# Strain_To_Digital.net
KiCad netlist of a schematic drawn in Altium Designer
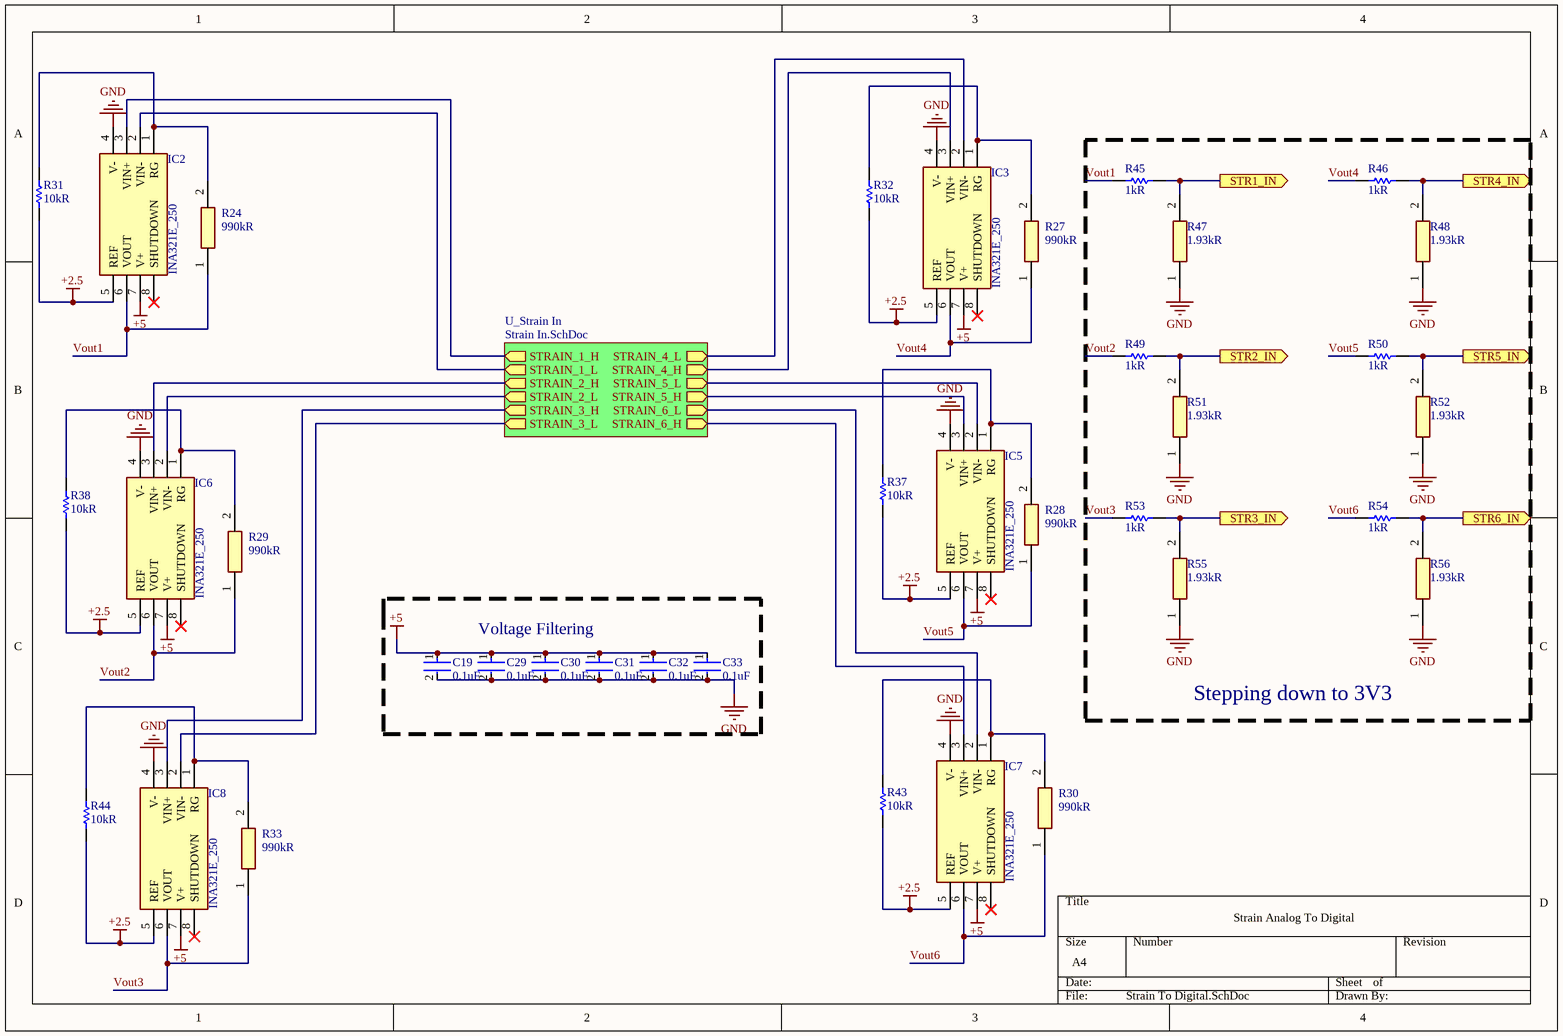
[diagram p0: Strain To Digital.SchDoc]

(export (version "E")
  (design (tool "Eeschema 10.0.6"))
  (components
    (comp (ref "C19")
      (value "0.1uF")
      (footprint "FP-CC0402-MFG")
      (description "CAP CER 0.1UF 16V X7R 0402")
      (fields (field (name "MANUFACTURER") "YAGEO") (field (name "TOLERANCE") "0.1"))
      (libsource (lib "Altium Content Vault") (part "11868f565c42a9108669ba33697ecf6"))
    )
    (comp (ref "C29")
      (value "0.1uF")
      (footprint "FP-CC0402-MFG")
      (description "CAP CER 0.1UF 16V X7R 0402")
      (fields (field (name "MANUFACTURER") "YAGEO") (field (name "TOLERANCE") "0.1"))
      (libsource (lib "Altium Content Vault") (part "11868f565c42a9108669ba33697ecf6"))
    )
    (comp (ref "C30")
      (value "0.1uF")
      (footprint "FP-CC0402-MFG")
      (description "CAP CER 0.1UF 16V X7R 0402")
      (fields (field (name "MANUFACTURER") "YAGEO") (field (name "TOLERANCE") "0.1"))
      (libsource (lib "Altium Content Vault") (part "11868f565c42a9108669ba33697ecf6"))
    )
    (comp (ref "C31")
      (value "0.1uF")
      (footprint "FP-CC0402-MFG")
      (description "CAP CER 0.1UF 16V X7R 0402")
      (fields (field (name "MANUFACTURER") "YAGEO") (field (name "TOLERANCE") "0.1"))
      (libsource (lib "Altium Content Vault") (part "11868f565c42a9108669ba33697ecf6"))
    )
    (comp (ref "C32")
      (value "0.1uF")
      (footprint "FP-CC0402-MFG")
      (description "CAP CER 0.1UF 16V X7R 0402")
      (fields (field (name "MANUFACTURER") "YAGEO") (field (name "TOLERANCE") "0.1"))
      (libsource (lib "Altium Content Vault") (part "11868f565c42a9108669ba33697ecf6"))
    )
    (comp (ref "C33")
      (value "0.1uF")
      (footprint "FP-CC0402-MFG")
      (description "CAP CER 0.1UF 16V X7R 0402")
      (fields (field (name "MANUFACTURER") "YAGEO") (field (name "TOLERANCE") "0.1"))
      (libsource (lib "Altium Content Vault") (part "11868f565c42a9108669ba33697ecf6"))
    )
    (comp (ref "IC2")
      (value "INA321E_250")
      (footprint "SamacSys:SOP65P490X110-8N")
      (description "Integrated Circuit")
      (fields (field (name "MANUFACTURER_PART_NUMBER") "INA321E/250"))
      (libsource (lib "*") (part "INA321E_250"))
    )
    (comp (ref "IC3")
      (value "INA321E_250")
      (footprint "SamacSys:SOP65P490X110-8N")
      (description "Integrated Circuit")
      (fields (field (name "MANUFACTURER_PART_NUMBER") "INA321E/250"))
      (libsource (lib "*") (part "INA321E_250"))
    )
    (comp (ref "IC5")
      (value "INA321E_250")
      (footprint "SamacSys:SOP65P490X110-8N")
      (description "Integrated Circuit")
      (fields (field (name "MANUFACTURER_PART_NUMBER") "INA321E/250"))
      (libsource (lib "*") (part "INA321E_250"))
    )
    (comp (ref "IC6")
      (value "INA321E_250")
      (footprint "SamacSys:SOP65P490X110-8N")
      (description "Integrated Circuit")
      (fields (field (name "MANUFACTURER_PART_NUMBER") "INA321E/250"))
      (libsource (lib "*") (part "INA321E_250"))
    )
    (comp (ref "IC7")
      (value "INA321E_250")
      (footprint "SamacSys:SOP65P490X110-8N")
      (description "Integrated Circuit")
      (fields (field (name "MANUFACTURER_PART_NUMBER") "INA321E/250"))
      (libsource (lib "*") (part "INA321E_250"))
    )
    (comp (ref "IC8")
      (value "INA321E_250")
      (footprint "SamacSys:SOP65P490X110-8N")
      (description "Integrated Circuit")
      (fields (field (name "MANUFACTURER_PART_NUMBER") "INA321E/250"))
      (libsource (lib "*") (part "INA321E_250"))
    )
    (comp (ref "R24")
      (value "990kR")
      (footprint "SamacSys:RESC3216X84N")
      (description "Resistor")
      (fields (field (name "MANUFACTURER_PART_NUMBER") "PTN1206E9903BST1"))
      (libsource (lib "*") (part "PTN1206E9903BST1"))
    )
    (comp (ref "R27")
      (value "990kR")
      (footprint "SamacSys:RESC3216X84N")
      (description "Resistor")
      (fields (field (name "MANUFACTURER_PART_NUMBER") "PTN1206E9903BST1"))
      (libsource (lib "*") (part "PTN1206E9903BST1"))
    )
    (comp (ref "R28")
      (value "990kR")
      (footprint "SamacSys:RESC3216X84N")
      (description "Resistor")
      (fields (field (name "MANUFACTURER_PART_NUMBER") "PTN1206E9903BST1"))
      (libsource (lib "*") (part "PTN1206E9903BST1"))
    )
    (comp (ref "R29")
      (value "990kR")
      (footprint "SamacSys:RESC3216X84N")
      (description "Resistor")
      (fields (field (name "MANUFACTURER_PART_NUMBER") "PTN1206E9903BST1"))
      (libsource (lib "*") (part "PTN1206E9903BST1"))
    )
    (comp (ref "R30")
      (value "990kR")
      (footprint "SamacSys:RESC3216X84N")
      (description "Resistor")
      (fields (field (name "MANUFACTURER_PART_NUMBER") "PTN1206E9903BST1"))
      (libsource (lib "*") (part "PTN1206E9903BST1"))
    )
    (comp (ref "R31")
      (value "10kR")
      (footprint "RESC1608X55X30ML20T20")
      (fields (field (name "PART NUMBER") "ERA-3AEB103V") (field (name "MANUFACTURER") "Panasonic"))
      (libsource (lib "Altium Content Vault") (part "RES"))
    )
    (comp (ref "R32")
      (value "10kR")
      (footprint "RESC1608X55X30ML20T20")
      (fields (field (name "PART NUMBER") "ERA-3AEB103V") (field (name "MANUFACTURER") "Panasonic"))
      (libsource (lib "Altium Content Vault") (part "RES"))
    )
    (comp (ref "R33")
      (value "990kR")
      (footprint "SamacSys:RESC3216X84N")
      (description "Resistor")
      (fields (field (name "MANUFACTURER_PART_NUMBER") "PTN1206E9903BST1"))
      (libsource (lib "*") (part "PTN1206E9903BST1"))
    )
    (comp (ref "R37")
      (value "10kR")
      (footprint "RESC1608X55X30ML20T20")
      (fields (field (name "PART NUMBER") "ERA-3AEB103V") (field (name "MANUFACTURER") "Panasonic"))
      (libsource (lib "Altium Content Vault") (part "RES"))
    )
    (comp (ref "R38")
      (value "10kR")
      (footprint "RESC1608X55X30ML20T20")
      (fields (field (name "PART NUMBER") "ERA-3AEB103V") (field (name "MANUFACTURER") "Panasonic"))
      (libsource (lib "Altium Content Vault") (part "RES"))
    )
    (comp (ref "R43")
      (value "10kR")
      (footprint "RESC1608X55X30ML20T20")
      (fields (field (name "PART NUMBER") "ERA-3AEB103V") (field (name "MANUFACTURER") "Panasonic"))
      (libsource (lib "Altium Content Vault") (part "RES"))
    )
    (comp (ref "R44")
      (value "10kR")
      (footprint "RESC1608X55X30ML20T20")
      (fields (field (name "PART NUMBER") "ERA-3AEB103V") (field (name "MANUFACTURER") "Panasonic"))
      (libsource (lib "Altium Content Vault") (part "RES"))
    )
    (comp (ref "R45")
      (value "1kR")
      (footprint "RESC2013X50X30NL20T20")
      (fields (field (name "PART NUMBER") "CRCW08051K00FKEA") (field (name "MANUFACTURER") "Vishay Dale"))
      (libsource (lib "Altium Content Vault") (part "RES"))
    )
    (comp (ref "R46")
      (value "1kR")
      (footprint "RESC2013X50X30NL20T20")
      (fields (field (name "PART NUMBER") "CRCW08051K00FKEA") (field (name "MANUFACTURER") "Vishay Dale"))
      (libsource (lib "Altium Content Vault") (part "RES"))
    )
    (comp (ref "R47")
      (value "1.93kR")
      (footprint "TNPW04021K93BEED")
      (description "Resistor")
      (fields (field (name "MANUFACTURER_PART_NUMBER") "KTR10EZPF1694"))
      (libsource (lib "SamacSys") (part "TNPW04021K93BEED"))
    )
    (comp (ref "R48")
      (value "1.93kR")
      (footprint "TNPW04021K93BEED")
      (description "Resistor")
      (fields (field (name "MANUFACTURER_PART_NUMBER") "KTR10EZPF1694"))
      (libsource (lib "SamacSys") (part "TNPW04021K93BEED"))
    )
    (comp (ref "R49")
      (value "1kR")
      (footprint "RESC2013X50X30NL20T20")
      (fields (field (name "PART NUMBER") "CRCW08051K00FKEA") (field (name "MANUFACTURER") "Vishay Dale"))
      (libsource (lib "Altium Content Vault") (part "RES"))
    )
    (comp (ref "R50")
      (value "1kR")
      (footprint "RESC2013X50X30NL20T20")
      (fields (field (name "PART NUMBER") "CRCW08051K00FKEA") (field (name "MANUFACTURER") "Vishay Dale"))
      (libsource (lib "Altium Content Vault") (part "RES"))
    )
    (comp (ref "R51")
      (value "1.93kR")
      (footprint "TNPW04021K93BEED")
      (description "Resistor")
      (fields (field (name "MANUFACTURER_PART_NUMBER") "KTR10EZPF1694"))
      (libsource (lib "SamacSys") (part "TNPW04021K93BEED"))
    )
    (comp (ref "R52")
      (value "1.93kR")
      (footprint "TNPW04021K93BEED")
      (description "Resistor")
      (fields (field (name "MANUFACTURER_PART_NUMBER") "KTR10EZPF1694"))
      (libsource (lib "SamacSys") (part "TNPW04021K93BEED"))
    )
    (comp (ref "R53")
      (value "1kR")
      (footprint "RESC2013X50X30NL20T20")
      (fields (field (name "PART NUMBER") "CRCW08051K00FKEA") (field (name "MANUFACTURER") "Vishay Dale"))
      (libsource (lib "Altium Content Vault") (part "RES"))
    )
    (comp (ref "R54")
      (value "1kR")
      (footprint "RESC2013X50X30NL20T20")
      (fields (field (name "PART NUMBER") "CRCW08051K00FKEA") (field (name "MANUFACTURER") "Vishay Dale"))
      (libsource (lib "Altium Content Vault") (part "RES"))
    )
    (comp (ref "R55")
      (value "1.93kR")
      (footprint "TNPW04021K93BEED")
      (description "Resistor")
      (fields (field (name "MANUFACTURER_PART_NUMBER") "KTR10EZPF1694"))
      (libsource (lib "SamacSys") (part "TNPW04021K93BEED"))
    )
    (comp (ref "R56")
      (value "1.93kR")
      (footprint "TNPW04021K93BEED")
      (description "Resistor")
      (fields (field (name "MANUFACTURER_PART_NUMBER") "KTR10EZPF1694"))
      (libsource (lib "SamacSys") (part "TNPW04021K93BEED"))
    )
  )
  (nets
    (net (code "1") (name "+2.5") (class "Default")
      (node (ref "IC2") (pin "5") (pinfunction "REF_5") (pintype "passive"))
      (node (ref "IC3") (pin "5") (pinfunction "REF_5") (pintype "passive"))
      (node (ref "IC5") (pin "5") (pinfunction "REF_5") (pintype "passive"))
      (node (ref "IC6") (pin "5") (pinfunction "REF_5") (pintype "passive"))
      (node (ref "IC7") (pin "5") (pinfunction "REF_5") (pintype "passive"))
      (node (ref "IC8") (pin "5") (pinfunction "REF_5") (pintype "passive"))
      (node (ref "R31") (pin "2") (pinfunction "2_2") (pintype "passive"))
      (node (ref "R32") (pin "2") (pinfunction "2_2") (pintype "passive"))
      (node (ref "R37") (pin "2") (pinfunction "2_2") (pintype "passive"))
      (node (ref "R38") (pin "2") (pinfunction "2_2") (pintype "passive"))
      (node (ref "R43") (pin "2") (pinfunction "2_2") (pintype "passive"))
      (node (ref "R44") (pin "2") (pinfunction "2_2") (pintype "passive"))
    )
    (net (code "2") (name "+5") (class "Default")
      (node (ref "C19") (pin "1") (pinfunction "1_1") (pintype "passive"))
      (node (ref "C29") (pin "1") (pinfunction "1_1") (pintype "passive"))
      (node (ref "C30") (pin "1") (pinfunction "1_1") (pintype "passive"))
      (node (ref "C31") (pin "1") (pinfunction "1_1") (pintype "passive"))
      (node (ref "C32") (pin "1") (pinfunction "1_1") (pintype "passive"))
      (node (ref "C33") (pin "1") (pinfunction "1_1") (pintype "passive"))
      (node (ref "IC2") (pin "7") (pinfunction "V+_7") (pintype "passive"))
      (node (ref "IC3") (pin "7") (pinfunction "V+_7") (pintype "passive"))
      (node (ref "IC5") (pin "7") (pinfunction "V+_7") (pintype "passive"))
      (node (ref "IC6") (pin "7") (pinfunction "V+_7") (pintype "passive"))
      (node (ref "IC7") (pin "7") (pinfunction "V+_7") (pintype "passive"))
      (node (ref "IC8") (pin "7") (pinfunction "V+_7") (pintype "passive"))
    )
    (net (code "3") (name "/STR1_IN") (class "Default")
      (node (ref "R45") (pin "2") (pinfunction "2_2") (pintype "passive"))
      (node (ref "R47") (pin "2") (pinfunction "2_2") (pintype "passive"))
    )
    (net (code "4") (name "/STR2_IN") (class "Default")
      (node (ref "R49") (pin "2") (pinfunction "2_2") (pintype "passive"))
      (node (ref "R51") (pin "2") (pinfunction "2_2") (pintype "passive"))
    )
    (net (code "5") (name "/STR3_IN") (class "Default")
      (node (ref "R53") (pin "2") (pinfunction "2_2") (pintype "passive"))
      (node (ref "R55") (pin "2") (pinfunction "2_2") (pintype "passive"))
    )
    (net (code "6") (name "/STR4_IN") (class "Default")
      (node (ref "R46") (pin "2") (pinfunction "2_2") (pintype "passive"))
      (node (ref "R48") (pin "2") (pinfunction "2_2") (pintype "passive"))
    )
    (net (code "7") (name "/STR5_IN") (class "Default")
      (node (ref "R50") (pin "2") (pinfunction "2_2") (pintype "passive"))
      (node (ref "R52") (pin "2") (pinfunction "2_2") (pintype "passive"))
    )
    (net (code "8") (name "/STR6_IN") (class "Default")
      (node (ref "R54") (pin "2") (pinfunction "2_2") (pintype "passive"))
      (node (ref "R56") (pin "2") (pinfunction "2_2") (pintype "passive"))
    )
    (net (code "9") (name "/STRAIN_1_H") (class "Default")
      (node (ref "IC2") (pin "3") (pinfunction "VIN+_3") (pintype "passive"))
    )
    (net (code "10") (name "/STRAIN_1_L") (class "Default")
      (node (ref "IC2") (pin "2") (pinfunction "VIN-_2") (pintype "passive"))
    )
    (net (code "11") (name "/STRAIN_2_H") (class "Default")
      (node (ref "IC6") (pin "3") (pinfunction "VIN+_3") (pintype "passive"))
    )
    (net (code "12") (name "/STRAIN_2_L") (class "Default")
      (node (ref "IC6") (pin "2") (pinfunction "VIN-_2") (pintype "passive"))
    )
    (net (code "13") (name "/STRAIN_3_H") (class "Default")
      (node (ref "IC8") (pin "3") (pinfunction "VIN+_3") (pintype "passive"))
    )
    (net (code "14") (name "/STRAIN_3_L") (class "Default")
      (node (ref "IC8") (pin "2") (pinfunction "VIN-_2") (pintype "passive"))
    )
    (net (code "15") (name "/STRAIN_4_H") (class "Default")
      (node (ref "IC3") (pin "3") (pinfunction "VIN+_3") (pintype "passive"))
    )
    (net (code "16") (name "/STRAIN_4_L") (class "Default")
      (node (ref "IC3") (pin "2") (pinfunction "VIN-_2") (pintype "passive"))
    )
    (net (code "17") (name "/STRAIN_5_H") (class "Default")
      (node (ref "IC5") (pin "3") (pinfunction "VIN+_3") (pintype "passive"))
    )
    (net (code "18") (name "/STRAIN_5_L") (class "Default")
      (node (ref "IC5") (pin "2") (pinfunction "VIN-_2") (pintype "passive"))
    )
    (net (code "19") (name "/STRAIN_6_H") (class "Default")
      (node (ref "IC7") (pin "3") (pinfunction "VIN+_3") (pintype "passive"))
    )
    (net (code "20") (name "/STRAIN_6_L") (class "Default")
      (node (ref "IC7") (pin "2") (pinfunction "VIN-_2") (pintype "passive"))
    )
    (net (code "21") (name "/Vout1") (class "Default")
      (node (ref "IC2") (pin "6") (pinfunction "VOUT_6") (pintype "passive"))
      (node (ref "R24") (pin "1") (pinfunction "1_1") (pintype "passive"))
      (node (ref "R45") (pin "1") (pinfunction "1_1") (pintype "passive"))
    )
    (net (code "22") (name "/Vout2") (class "Default")
      (node (ref "IC6") (pin "6") (pinfunction "VOUT_6") (pintype "passive"))
      (node (ref "R29") (pin "1") (pinfunction "1_1") (pintype "passive"))
      (node (ref "R49") (pin "1") (pinfunction "1_1") (pintype "passive"))
    )
    (net (code "23") (name "/Vout3") (class "Default")
      (node (ref "IC8") (pin "6") (pinfunction "VOUT_6") (pintype "passive"))
      (node (ref "R33") (pin "1") (pinfunction "1_1") (pintype "passive"))
      (node (ref "R53") (pin "1") (pinfunction "1_1") (pintype "passive"))
    )
    (net (code "24") (name "/Vout4") (class "Default")
      (node (ref "IC3") (pin "6") (pinfunction "VOUT_6") (pintype "passive"))
      (node (ref "R27") (pin "1") (pinfunction "1_1") (pintype "passive"))
      (node (ref "R46") (pin "1") (pinfunction "1_1") (pintype "passive"))
    )
    (net (code "25") (name "/Vout5") (class "Default")
      (node (ref "IC5") (pin "6") (pinfunction "VOUT_6") (pintype "passive"))
      (node (ref "R28") (pin "1") (pinfunction "1_1") (pintype "passive"))
      (node (ref "R50") (pin "1") (pinfunction "1_1") (pintype "passive"))
    )
    (net (code "26") (name "/Vout6") (class "Default")
      (node (ref "IC7") (pin "6") (pinfunction "VOUT_6") (pintype "passive"))
      (node (ref "R30") (pin "1") (pinfunction "1_1") (pintype "passive"))
      (node (ref "R54") (pin "1") (pinfunction "1_1") (pintype "passive"))
    )
    (net (code "27") (name "GND") (class "Default")
      (node (ref "C19") (pin "2") (pinfunction "2_2") (pintype "passive"))
      (node (ref "C29") (pin "2") (pinfunction "2_2") (pintype "passive"))
      (node (ref "C30") (pin "2") (pinfunction "2_2") (pintype "passive"))
      (node (ref "C31") (pin "2") (pinfunction "2_2") (pintype "passive"))
      (node (ref "C32") (pin "2") (pinfunction "2_2") (pintype "passive"))
      (node (ref "C33") (pin "2") (pinfunction "2_2") (pintype "passive"))
      (node (ref "IC2") (pin "4") (pinfunction "V-_4") (pintype "passive"))
      (node (ref "IC3") (pin "4") (pinfunction "V-_4") (pintype "passive"))
      (node (ref "IC5") (pin "4") (pinfunction "V-_4") (pintype "passive"))
      (node (ref "IC6") (pin "4") (pinfunction "V-_4") (pintype "passive"))
      (node (ref "IC7") (pin "4") (pinfunction "V-_4") (pintype "passive"))
      (node (ref "IC8") (pin "4") (pinfunction "V-_4") (pintype "passive"))
      (node (ref "R47") (pin "1") (pinfunction "1_1") (pintype "passive"))
      (node (ref "R48") (pin "1") (pinfunction "1_1") (pintype "passive"))
      (node (ref "R51") (pin "1") (pinfunction "1_1") (pintype "passive"))
      (node (ref "R52") (pin "1") (pinfunction "1_1") (pintype "passive"))
      (node (ref "R55") (pin "1") (pinfunction "1_1") (pintype "passive"))
      (node (ref "R56") (pin "1") (pinfunction "1_1") (pintype "passive"))
    )
    (net (code "28") (name "Net-(IC2-RG)") (class "Default")
      (node (ref "IC2") (pin "1") (pinfunction "RG_1") (pintype "passive"))
      (node (ref "R24") (pin "2") (pinfunction "2_2") (pintype "passive"))
      (node (ref "R31") (pin "1") (pinfunction "1_1") (pintype "passive"))
    )
    (net (code "29") (name "Net-(IC3-RG)") (class "Default")
      (node (ref "IC3") (pin "1") (pinfunction "RG_1") (pintype "passive"))
      (node (ref "R27") (pin "2") (pinfunction "2_2") (pintype "passive"))
      (node (ref "R32") (pin "1") (pinfunction "1_1") (pintype "passive"))
    )
    (net (code "30") (name "Net-(IC5-RG)") (class "Default")
      (node (ref "IC5") (pin "1") (pinfunction "RG_1") (pintype "passive"))
      (node (ref "R28") (pin "2") (pinfunction "2_2") (pintype "passive"))
      (node (ref "R37") (pin "1") (pinfunction "1_1") (pintype "passive"))
    )
    (net (code "31") (name "Net-(IC6-RG)") (class "Default")
      (node (ref "IC6") (pin "1") (pinfunction "RG_1") (pintype "passive"))
      (node (ref "R29") (pin "2") (pinfunction "2_2") (pintype "passive"))
      (node (ref "R38") (pin "1") (pinfunction "1_1") (pintype "passive"))
    )
    (net (code "32") (name "Net-(IC7-RG)") (class "Default")
      (node (ref "IC7") (pin "1") (pinfunction "RG_1") (pintype "passive"))
      (node (ref "R30") (pin "2") (pinfunction "2_2") (pintype "passive"))
      (node (ref "R43") (pin "1") (pinfunction "1_1") (pintype "passive"))
    )
    (net (code "33") (name "Net-(IC8-RG)") (class "Default")
      (node (ref "IC8") (pin "1") (pinfunction "RG_1") (pintype "passive"))
      (node (ref "R33") (pin "2") (pinfunction "2_2") (pintype "passive"))
      (node (ref "R44") (pin "1") (pinfunction "1_1") (pintype "passive"))
    )
    (net (code "34") (name "unconnected-(IC2-SHUTDOWN-Pad8)") (class "Default")
      (node (ref "IC2") (pin "8") (pinfunction "SHUTDOWN_8") (pintype "passive+no_connect"))
    )
    (net (code "35") (name "unconnected-(IC3-SHUTDOWN-Pad8)") (class "Default")
      (node (ref "IC3") (pin "8") (pinfunction "SHUTDOWN_8") (pintype "passive+no_connect"))
    )
    (net (code "36") (name "unconnected-(IC5-SHUTDOWN-Pad8)") (class "Default")
      (node (ref "IC5") (pin "8") (pinfunction "SHUTDOWN_8") (pintype "passive+no_connect"))
    )
    (net (code "37") (name "unconnected-(IC6-SHUTDOWN-Pad8)") (class "Default")
      (node (ref "IC6") (pin "8") (pinfunction "SHUTDOWN_8") (pintype "passive+no_connect"))
    )
    (net (code "38") (name "unconnected-(IC7-SHUTDOWN-Pad8)") (class "Default")
      (node (ref "IC7") (pin "8") (pinfunction "SHUTDOWN_8") (pintype "passive+no_connect"))
    )
    (net (code "39") (name "unconnected-(IC8-SHUTDOWN-Pad8)") (class "Default")
      (node (ref "IC8") (pin "8") (pinfunction "SHUTDOWN_8") (pintype "passive+no_connect"))
    )
  )
)
